# ts7_redraw.net
KiCad netlist of a schematic drawn in EAGLE
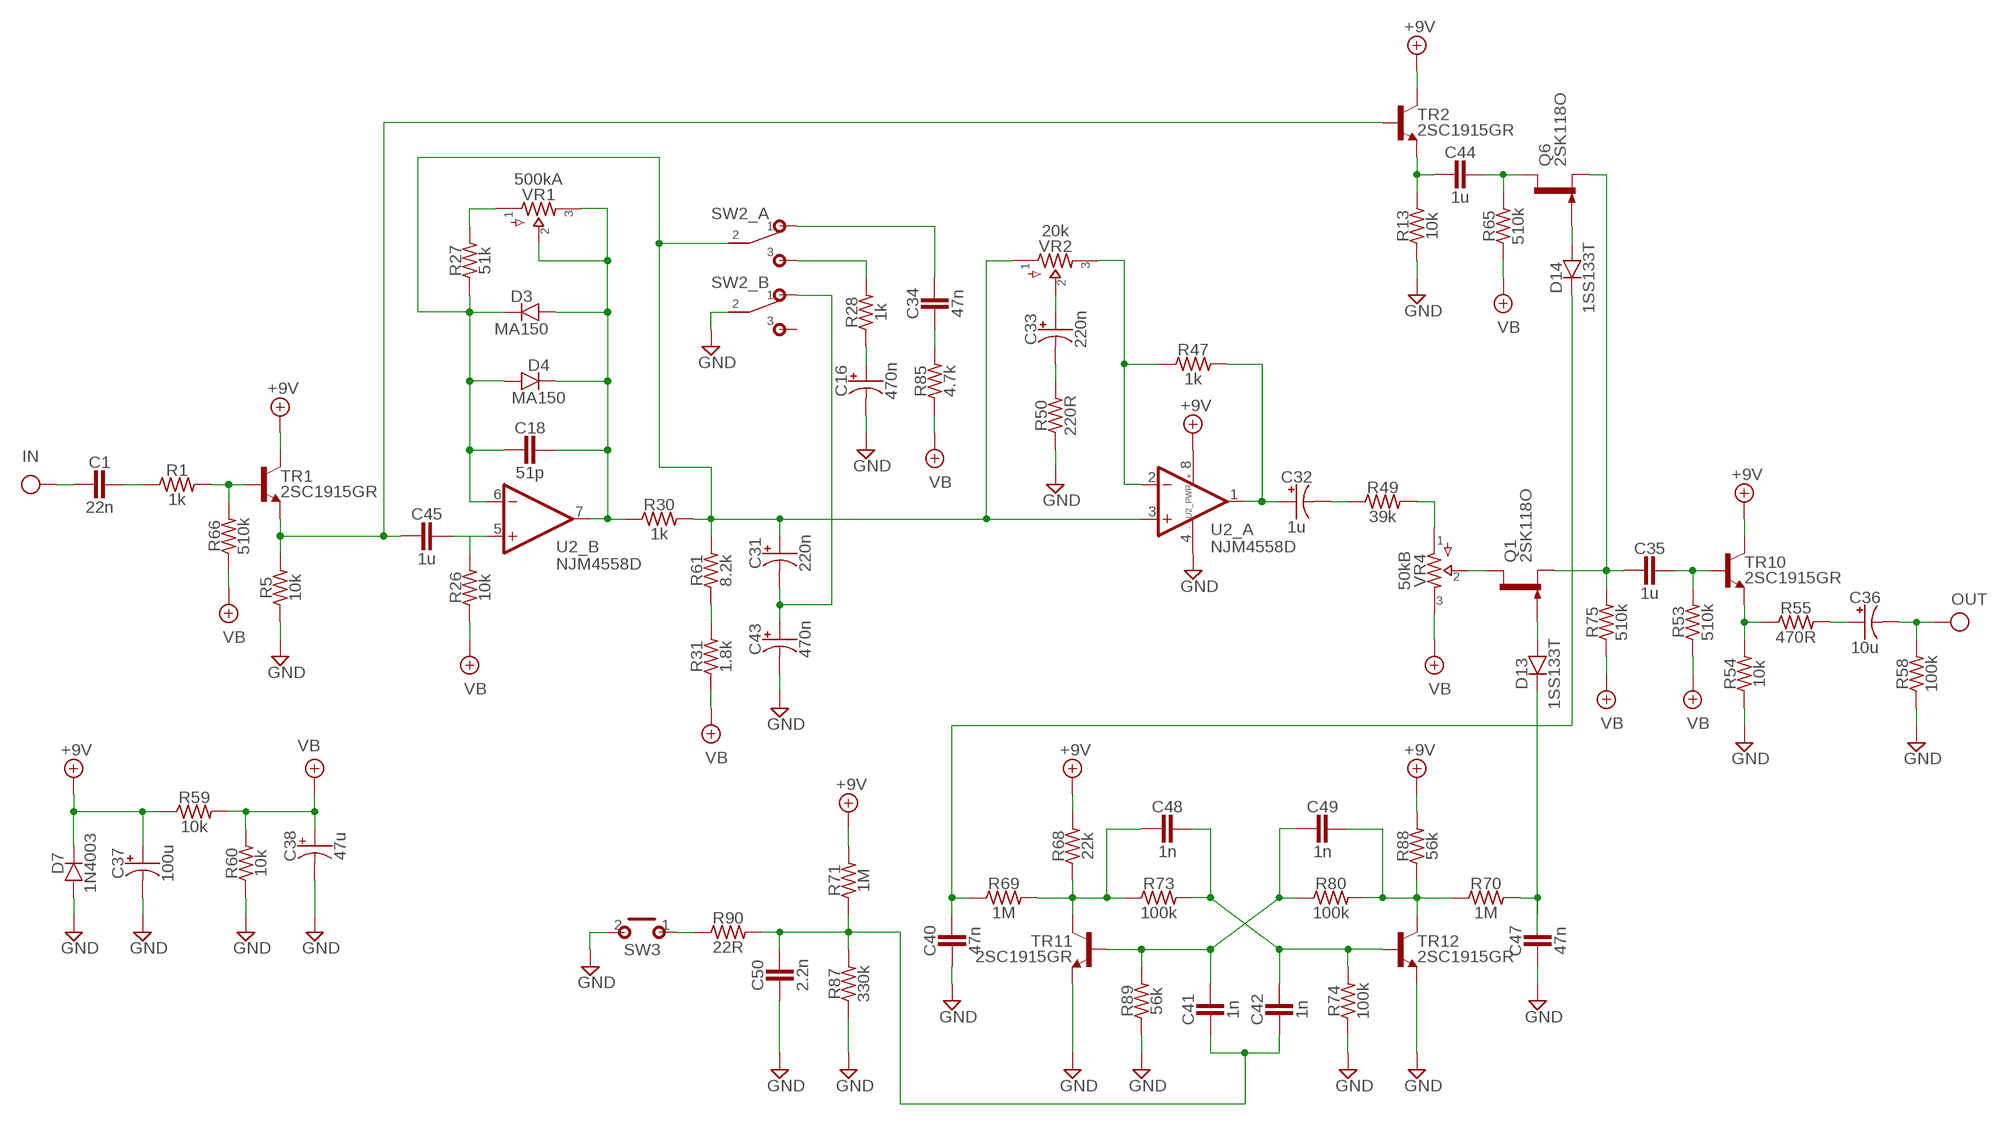
[diagram p0: schematic, sheet 1]

(export (version "E")
  (design (tool "Eeschema 10.0.6"))
  (components
    (comp (ref "C1")
      (value "22n")
      (footprint "eagle-import:BOX_SMALL")
      (libsource (lib "eagle-import") (part "CER/FILMBOX.1"))
    )
    (comp (ref "C16")
      (value "470n")
      (footprint "eagle-import:040_020")
      (libsource (lib "eagle-import") (part "0400"))
    )
    (comp (ref "C18")
      (value "51p")
      (footprint "eagle-import:BOX_SMALL")
      (libsource (lib "eagle-import") (part "CER/FILMBOX.1"))
    )
    (comp (ref "C31")
      (value "220n")
      (footprint "eagle-import:040_020")
      (libsource (lib "eagle-import") (part "0400"))
    )
    (comp (ref "C32")
      (value "1u")
      (footprint "eagle-import:040_020")
      (libsource (lib "eagle-import") (part "0400"))
    )
    (comp (ref "C33")
      (value "220n")
      (footprint "eagle-import:040_020")
      (libsource (lib "eagle-import") (part "0400"))
    )
    (comp (ref "C34")
      (value "47n")
      (footprint "eagle-import:BOX_SMALL")
      (libsource (lib "eagle-import") (part "CER/FILMBOX.1"))
    )
    (comp (ref "C35")
      (value "1u")
      (footprint "eagle-import:BOX_SMALL")
      (libsource (lib "eagle-import") (part "CER/FILMBOX.1"))
    )
    (comp (ref "C36")
      (value "10u")
      (footprint "eagle-import:040_020")
      (libsource (lib "eagle-import") (part "0400"))
    )
    (comp (ref "C37")
      (value "100u")
      (footprint "eagle-import:040_020")
      (libsource (lib "eagle-import") (part "0400"))
    )
    (comp (ref "C38")
      (value "47u")
      (footprint "eagle-import:040_020")
      (libsource (lib "eagle-import") (part "0400"))
    )
    (comp (ref "C40")
      (value "47n")
      (footprint "eagle-import:BOX_SMALL")
      (libsource (lib "eagle-import") (part "CER/FILMBOX.1"))
    )
    (comp (ref "C41")
      (value "1n")
      (footprint "eagle-import:BOX_SMALL")
      (libsource (lib "eagle-import") (part "CER/FILMBOX.1"))
    )
    (comp (ref "C42")
      (value "1n")
      (footprint "eagle-import:BOX_SMALL")
      (libsource (lib "eagle-import") (part "CER/FILMBOX.1"))
    )
    (comp (ref "C43")
      (value "470n")
      (footprint "eagle-import:040_020")
      (libsource (lib "eagle-import") (part "0400"))
    )
    (comp (ref "C44")
      (value "1u")
      (footprint "eagle-import:BOX_SMALL")
      (libsource (lib "eagle-import") (part "CER/FILMBOX.1"))
    )
    (comp (ref "C45")
      (value "1u")
      (footprint "eagle-import:BOX_SMALL")
      (libsource (lib "eagle-import") (part "CER/FILMBOX.1"))
    )
    (comp (ref "C47")
      (value "47n")
      (footprint "eagle-import:BOX_SMALL")
      (libsource (lib "eagle-import") (part "CER/FILMBOX.1"))
    )
    (comp (ref "C48")
      (value "1n")
      (footprint "eagle-import:BOX_SMALL")
      (libsource (lib "eagle-import") (part "CER/FILMBOX.1"))
    )
    (comp (ref "C49")
      (value "1n")
      (footprint "eagle-import:BOX_SMALL")
      (libsource (lib "eagle-import") (part "CER/FILMBOX.1"))
    )
    (comp (ref "C50")
      (value "2.2n")
      (footprint "eagle-import:BOX_SMALL")
      (libsource (lib "eagle-import") (part "CER/FILMBOX.1"))
    )
    (comp (ref "D3")
      (value "MA150")
      (footprint "eagle-import:DO41-2")
      (libsource (lib "eagle-import") (part "DO41.2"))
    )
    (comp (ref "D4")
      (value "MA150")
      (footprint "eagle-import:DO41-2")
      (libsource (lib "eagle-import") (part "DO41.2"))
    )
    (comp (ref "D7")
      (value "1N4003")
      (footprint "eagle-import:DO41-2")
      (libsource (lib "eagle-import") (part "DO41.2"))
    )
    (comp (ref "D13")
      (value "1SS133T")
      (footprint "eagle-import:DO41-2")
      (libsource (lib "eagle-import") (part "DO41.2"))
    )
    (comp (ref "D14")
      (value "1SS133T")
      (footprint "eagle-import:DO41-2")
      (libsource (lib "eagle-import") (part "DO41.2"))
    )
    (comp (ref "Q1")
      (value "2SK118O")
      (footprint "eagle-import:TO92-")
      (libsource (lib "eagle-import") (part "2N5457"))
    )
    (comp (ref "Q6")
      (value "2SK118O")
      (footprint "eagle-import:TO92-")
      (libsource (lib "eagle-import") (part "2N5457"))
    )
    (comp (ref "R1")
      (value "1k")
      (footprint "eagle-import:R0207_3")
      (libsource (lib "eagle-import") (part "R_.3B"))
    )
    (comp (ref "R5")
      (value "10k")
      (footprint "eagle-import:R0207_3")
      (libsource (lib "eagle-import") (part "R_.3B"))
    )
    (comp (ref "R13")
      (value "10k")
      (footprint "eagle-import:R0207_3")
      (libsource (lib "eagle-import") (part "R_.3B"))
    )
    (comp (ref "R26")
      (value "10k")
      (footprint "eagle-import:R0207_3")
      (libsource (lib "eagle-import") (part "R_.3B"))
    )
    (comp (ref "R27")
      (value "51k")
      (footprint "eagle-import:R0207_3")
      (libsource (lib "eagle-import") (part "R_.3B"))
    )
    (comp (ref "R28")
      (value "1k")
      (footprint "eagle-import:R0207_3")
      (libsource (lib "eagle-import") (part "R_.3B"))
    )
    (comp (ref "R30")
      (value "1k")
      (footprint "eagle-import:R0207_3")
      (libsource (lib "eagle-import") (part "R_.3B"))
    )
    (comp (ref "R31")
      (value "1.8k")
      (footprint "eagle-import:R0207_3")
      (libsource (lib "eagle-import") (part "R_.3B"))
    )
    (comp (ref "R47")
      (value "1k")
      (footprint "eagle-import:R0207_3")
      (libsource (lib "eagle-import") (part "R_.3B"))
    )
    (comp (ref "R49")
      (value "39k")
      (footprint "eagle-import:R0207_3")
      (libsource (lib "eagle-import") (part "R_.3B"))
    )
    (comp (ref "R50")
      (value "220R")
      (footprint "eagle-import:R0207_3")
      (libsource (lib "eagle-import") (part "R_.3B"))
    )
    (comp (ref "R53")
      (value "510k")
      (footprint "eagle-import:R0207_3")
      (libsource (lib "eagle-import") (part "R_.3B"))
    )
    (comp (ref "R54")
      (value "10k")
      (footprint "eagle-import:R0207_3")
      (libsource (lib "eagle-import") (part "R_.3B"))
    )
    (comp (ref "R55")
      (value "470R")
      (footprint "eagle-import:R0207_3")
      (libsource (lib "eagle-import") (part "R_.3B"))
    )
    (comp (ref "R58")
      (value "100k")
      (footprint "eagle-import:R0207_3")
      (libsource (lib "eagle-import") (part "R_.3B"))
    )
    (comp (ref "R59")
      (value "10k")
      (footprint "eagle-import:R0207_3")
      (libsource (lib "eagle-import") (part "R_.3B"))
    )
    (comp (ref "R60")
      (value "10k")
      (footprint "eagle-import:R0207_3")
      (libsource (lib "eagle-import") (part "R_.3B"))
    )
    (comp (ref "R61")
      (value "8.2k")
      (footprint "eagle-import:R0207_3")
      (libsource (lib "eagle-import") (part "R_.3B"))
    )
    (comp (ref "R65")
      (value "510k")
      (footprint "eagle-import:R0207_3")
      (libsource (lib "eagle-import") (part "R_.3B"))
    )
    (comp (ref "R66")
      (value "510k")
      (footprint "eagle-import:R0207_3")
      (libsource (lib "eagle-import") (part "R_.3B"))
    )
    (comp (ref "R68")
      (value "22k")
      (footprint "eagle-import:R0207_3")
      (libsource (lib "eagle-import") (part "R_.3B"))
    )
    (comp (ref "R69")
      (value "1M")
      (footprint "eagle-import:R0207_3")
      (libsource (lib "eagle-import") (part "R_.3B"))
    )
    (comp (ref "R70")
      (value "1M")
      (footprint "eagle-import:R0207_3")
      (libsource (lib "eagle-import") (part "R_.3B"))
    )
    (comp (ref "R71")
      (value "1M")
      (footprint "eagle-import:R0207_3")
      (libsource (lib "eagle-import") (part "R_.3B"))
    )
    (comp (ref "R73")
      (value "100k")
      (footprint "eagle-import:R0207_3")
      (libsource (lib "eagle-import") (part "R_.3B"))
    )
    (comp (ref "R74")
      (value "100k")
      (footprint "eagle-import:R0207_3")
      (libsource (lib "eagle-import") (part "R_.3B"))
    )
    (comp (ref "R75")
      (value "510k")
      (footprint "eagle-import:R0207_3")
      (libsource (lib "eagle-import") (part "R_.3B"))
    )
    (comp (ref "R80")
      (value "100k")
      (footprint "eagle-import:R0207_3")
      (libsource (lib "eagle-import") (part "R_.3B"))
    )
    (comp (ref "R85")
      (value "4.7k")
      (footprint "eagle-import:R0207_3")
      (libsource (lib "eagle-import") (part "R_.3B"))
    )
    (comp (ref "R87")
      (value "330k")
      (footprint "eagle-import:R0207_3")
      (libsource (lib "eagle-import") (part "R_.3B"))
    )
    (comp (ref "R88")
      (value "56k")
      (footprint "eagle-import:R0207_3")
      (libsource (lib "eagle-import") (part "R_.3B"))
    )
    (comp (ref "R89")
      (value "56k")
      (footprint "eagle-import:R0207_3")
      (libsource (lib "eagle-import") (part "R_.3B"))
    )
    (comp (ref "R90")
      (value "22R")
      (footprint "eagle-import:R0207_3")
      (libsource (lib "eagle-import") (part "R_.3B"))
    )
    (comp (ref "SW2")
      (value "DPDT")
      (footprint "eagle-import:DPDT")
      (libsource (lib "eagle-import") (part "DPDT"))
    )
    (comp (ref "SW3")
      (value "MOMENTARY")
      (footprint "eagle-import:SPST")
      (libsource (lib "eagle-import") (part "MOMENTARY"))
    )
    (comp (ref "TR1")
      (value "2SC1915GR")
      (footprint "eagle-import:TO92-")
      (libsource (lib "eagle-import") (part "2SC828A"))
    )
    (comp (ref "TR2")
      (value "2SC1915GR")
      (footprint "eagle-import:TO92-")
      (libsource (lib "eagle-import") (part "2SC828A"))
    )
    (comp (ref "TR10")
      (value "2SC1915GR")
      (footprint "eagle-import:TO92-")
      (libsource (lib "eagle-import") (part "2SC828A"))
    )
    (comp (ref "TR11")
      (value "2SC1915GR")
      (footprint "eagle-import:TO92-")
      (libsource (lib "eagle-import") (part "2SC828A"))
    )
    (comp (ref "TR12")
      (value "2SC1915GR")
      (footprint "eagle-import:TO92-")
      (libsource (lib "eagle-import") (part "2SC828A"))
    )
    (comp (ref "U2")
      (value "NJM4558D")
      (footprint "eagle-import:DIL0")
      (libsource (lib "eagle-import") (part "DUALTH"))
    )
    (comp (ref "VR1")
      (value "500kA")
      (footprint "eagle-import:16MM")
      (libsource (lib "eagle-import") (part "POTS16MM"))
    )
    (comp (ref "VR2")
      (value "20k")
      (footprint "eagle-import:16MM")
      (libsource (lib "eagle-import") (part "POTS16MM"))
    )
    (comp (ref "VR4")
      (value "50kB")
      (footprint "eagle-import:16MM")
      (libsource (lib "eagle-import") (part "POTS16MM"))
    )
  )
  (nets
    (net (code "1") (name "+9V") (class "Default")
      (node (ref "C37") (pin "+") (pinfunction "+_+") (pintype "passive"))
      (node (ref "D7") (pin "C") (pinfunction "C_C") (pintype "passive"))
      (node (ref "R59") (pin "1") (pinfunction "1_1") (pintype "passive"))
      (node (ref "R68") (pin "2") (pinfunction "2_2") (pintype "passive"))
      (node (ref "R71") (pin "2") (pinfunction "2_2") (pintype "passive"))
      (node (ref "R88") (pin "2") (pinfunction "2_2") (pintype "passive"))
      (node (ref "TR1") (pin "2") (pinfunction "C_2") (pintype "passive"))
      (node (ref "TR10") (pin "2") (pinfunction "C_2") (pintype "passive"))
      (node (ref "TR2") (pin "2") (pinfunction "C_2") (pintype "passive"))
      (node (ref "U2") (pin "8") (pinfunction "V+_8") (pintype "power_in"))
    )
    (net (code "2") (name "GND") (class "Default")
      (node (ref "C16") (pin "-") (pinfunction "-_-") (pintype "passive"))
      (node (ref "C37") (pin "-") (pinfunction "-_-") (pintype "passive"))
      (node (ref "C38") (pin "-") (pinfunction "-_-") (pintype "passive"))
      (node (ref "C40") (pin "2") (pinfunction "2_2") (pintype "passive"))
      (node (ref "C43") (pin "-") (pinfunction "-_-") (pintype "passive"))
      (node (ref "C47") (pin "2") (pinfunction "2_2") (pintype "passive"))
      (node (ref "C50") (pin "2") (pinfunction "2_2") (pintype "passive"))
      (node (ref "D7") (pin "A") (pinfunction "A_A") (pintype "passive"))
      (node (ref "R13") (pin "1") (pinfunction "1_1") (pintype "passive"))
      (node (ref "R5") (pin "1") (pinfunction "1_1") (pintype "passive"))
      (node (ref "R50") (pin "1") (pinfunction "1_1") (pintype "passive"))
      (node (ref "R54") (pin "1") (pinfunction "1_1") (pintype "passive"))
      (node (ref "R58") (pin "1") (pinfunction "1_1") (pintype "passive"))
      (node (ref "R60") (pin "1") (pinfunction "1_1") (pintype "passive"))
      (node (ref "R74") (pin "1") (pinfunction "1_1") (pintype "passive"))
      (node (ref "R87") (pin "1") (pinfunction "1_1") (pintype "passive"))
      (node (ref "R89") (pin "1") (pinfunction "1_1") (pintype "passive"))
      (node (ref "SW2") (pin "B2") (pinfunction "2_B2") (pintype "passive"))
      (node (ref "SW3") (pin "2") (pinfunction "S_2") (pintype "passive"))
      (node (ref "TR11") (pin "3") (pinfunction "E_3") (pintype "passive"))
      (node (ref "TR12") (pin "3") (pinfunction "E_3") (pintype "passive"))
      (node (ref "U2") (pin "4") (pinfunction "V-_4") (pintype "power_in"))
    )
    (net (code "3") (name "IN") (class "Default")
      (node (ref "C1") (pin "2") (pinfunction "2_2") (pintype "passive"))
    )
    (net (code "4") (name "Net-(C1-Pad1)") (class "Default")
      (node (ref "C1") (pin "1") (pinfunction "1_1") (pintype "passive"))
      (node (ref "R1") (pin "1") (pinfunction "1_1") (pintype "passive"))
    )
    (net (code "5") (name "Net-(C16-Pad+)") (class "Default")
      (node (ref "C16") (pin "+") (pinfunction "+_+") (pintype "passive"))
      (node (ref "R28") (pin "1") (pinfunction "1_1") (pintype "passive"))
    )
    (net (code "6") (name "Net-(C32-Pad-)") (class "Default")
      (node (ref "C32") (pin "-") (pinfunction "-_-") (pintype "passive"))
      (node (ref "R49") (pin "1") (pinfunction "1_1") (pintype "passive"))
    )
    (net (code "7") (name "Net-(C33-Pad+)") (class "Default")
      (node (ref "C33") (pin "+") (pinfunction "+_+") (pintype "passive"))
      (node (ref "VR2") (pin "2") (pinfunction "2_2") (pintype "passive"))
    )
    (net (code "8") (name "Net-(C33-Pad-)") (class "Default")
      (node (ref "C33") (pin "-") (pinfunction "-_-") (pintype "passive"))
      (node (ref "R50") (pin "2") (pinfunction "2_2") (pintype "passive"))
    )
    (net (code "9") (name "Net-(C34-Pad2)") (class "Default")
      (node (ref "C34") (pin "2") (pinfunction "2_2") (pintype "passive"))
      (node (ref "R85") (pin "2") (pinfunction "2_2") (pintype "passive"))
    )
    (net (code "10") (name "Net-(C36-Pad+)") (class "Default")
      (node (ref "C36") (pin "+") (pinfunction "+_+") (pintype "passive"))
      (node (ref "R55") (pin "2") (pinfunction "2_2") (pintype "passive"))
    )
    (net (code "11") (name "Net-(C40-Pad1)") (class "Default")
      (node (ref "C40") (pin "1") (pinfunction "1_1") (pintype "passive"))
      (node (ref "D14") (pin "C") (pinfunction "C_C") (pintype "passive"))
      (node (ref "R69") (pin "1") (pinfunction "1_1") (pintype "passive"))
    )
    (net (code "12") (name "Net-(C41-Pad2)") (class "Default")
      (node (ref "C41") (pin "2") (pinfunction "2_2") (pintype "passive"))
      (node (ref "C42") (pin "2") (pinfunction "2_2") (pintype "passive"))
      (node (ref "C50") (pin "1") (pinfunction "1_1") (pintype "passive"))
      (node (ref "R71") (pin "1") (pinfunction "1_1") (pintype "passive"))
      (node (ref "R87") (pin "2") (pinfunction "2_2") (pintype "passive"))
      (node (ref "R90") (pin "2") (pinfunction "2_2") (pintype "passive"))
    )
    (net (code "13") (name "Net-(C47-Pad1)") (class "Default")
      (node (ref "C47") (pin "1") (pinfunction "1_1") (pintype "passive"))
      (node (ref "D13") (pin "C") (pinfunction "C_C") (pintype "passive"))
      (node (ref "R70") (pin "2") (pinfunction "2_2") (pintype "passive"))
    )
    (net (code "14") (name "Net-(Q1-D)") (class "Default")
      (node (ref "Q1") (pin "3") (pinfunction "D_3") (pintype "passive"))
      (node (ref "VR4") (pin "2") (pinfunction "2_2") (pintype "passive"))
    )
    (net (code "15") (name "Net-(Q1-G)") (class "Default")
      (node (ref "D13") (pin "A") (pinfunction "A_A") (pintype "passive"))
      (node (ref "Q1") (pin "1") (pinfunction "G_1") (pintype "passive"))
    )
    (net (code "16") (name "Net-(Q1-S)") (class "Default")
      (node (ref "C35") (pin "2") (pinfunction "2_2") (pintype "passive"))
      (node (ref "Q1") (pin "2") (pinfunction "S_2") (pintype "passive"))
      (node (ref "Q6") (pin "2") (pinfunction "S_2") (pintype "passive"))
      (node (ref "R75") (pin "2") (pinfunction "2_2") (pintype "passive"))
    )
    (net (code "17") (name "Net-(Q6-D)") (class "Default")
      (node (ref "C44") (pin "1") (pinfunction "1_1") (pintype "passive"))
      (node (ref "Q6") (pin "3") (pinfunction "D_3") (pintype "passive"))
      (node (ref "R65") (pin "2") (pinfunction "2_2") (pintype "passive"))
    )
    (net (code "18") (name "Net-(Q6-G)") (class "Default")
      (node (ref "D14") (pin "A") (pinfunction "A_A") (pintype "passive"))
      (node (ref "Q6") (pin "1") (pinfunction "G_1") (pintype "passive"))
    )
    (net (code "19") (name "Net-(R27-Pad2)") (class "Default")
      (node (ref "R27") (pin "2") (pinfunction "2_2") (pintype "passive"))
      (node (ref "VR1") (pin "1") (pinfunction "1_1") (pintype "passive"))
    )
    (net (code "20") (name "Net-(R31-Pad2)") (class "Default")
      (node (ref "R31") (pin "2") (pinfunction "2_2") (pintype "passive"))
      (node (ref "R61") (pin "1") (pinfunction "1_1") (pintype "passive"))
    )
    (net (code "21") (name "Net-(R49-Pad2)") (class "Default")
      (node (ref "R49") (pin "2") (pinfunction "2_2") (pintype "passive"))
      (node (ref "VR4") (pin "1") (pinfunction "1_1") (pintype "passive"))
    )
    (net (code "22") (name "Net-(SW2A-1)") (class "Default")
      (node (ref "C34") (pin "1") (pinfunction "1_1") (pintype "passive"))
      (node (ref "SW2") (pin "A1") (pinfunction "1_A1") (pintype "passive"))
    )
    (net (code "23") (name "Net-(SW2A-2)") (class "Default")
      (node (ref "C18") (pin "2") (pinfunction "2_2") (pintype "passive"))
      (node (ref "C31") (pin "+") (pinfunction "+_+") (pintype "passive"))
      (node (ref "D3") (pin "C") (pinfunction "C_C") (pintype "passive"))
      (node (ref "D4") (pin "A") (pinfunction "A_A") (pintype "passive"))
      (node (ref "R27") (pin "1") (pinfunction "1_1") (pintype "passive"))
      (node (ref "R30") (pin "2") (pinfunction "2_2") (pintype "passive"))
      (node (ref "R61") (pin "2") (pinfunction "2_2") (pintype "passive"))
      (node (ref "SW2") (pin "A2") (pinfunction "2_A2") (pintype "passive"))
      (node (ref "U2") (pin "3") (pinfunction "+IN_3") (pintype "input"))
      (node (ref "U2") (pin "6") (pinfunction "-IN_6") (pintype "input"))
      (node (ref "VR2") (pin "1") (pinfunction "1_1") (pintype "passive"))
    )
    (net (code "24") (name "Net-(SW2A-3)") (class "Default")
      (node (ref "R28") (pin "2") (pinfunction "2_2") (pintype "passive"))
      (node (ref "SW2") (pin "A3") (pinfunction "3_A3") (pintype "passive"))
    )
    (net (code "25") (name "Net-(SW2B-1)") (class "Default")
      (node (ref "C31") (pin "-") (pinfunction "-_-") (pintype "passive"))
      (node (ref "C43") (pin "+") (pinfunction "+_+") (pintype "passive"))
      (node (ref "SW2") (pin "B1") (pinfunction "1_B1") (pintype "passive"))
    )
    (net (code "26") (name "Net-(SW3-P)") (class "Default")
      (node (ref "R90") (pin "1") (pinfunction "1_1") (pintype "passive"))
      (node (ref "SW3") (pin "1") (pinfunction "P_1") (pintype "passive"))
    )
    (net (code "27") (name "Net-(TR1-B)") (class "Default")
      (node (ref "R1") (pin "2") (pinfunction "2_2") (pintype "passive"))
      (node (ref "R66") (pin "2") (pinfunction "2_2") (pintype "passive"))
      (node (ref "TR1") (pin "1") (pinfunction "B_1") (pintype "passive"))
    )
    (net (code "28") (name "Net-(TR1-E)") (class "Default")
      (node (ref "C45") (pin "2") (pinfunction "2_2") (pintype "passive"))
      (node (ref "R5") (pin "2") (pinfunction "2_2") (pintype "passive"))
      (node (ref "TR1") (pin "3") (pinfunction "E_3") (pintype "passive"))
      (node (ref "TR2") (pin "1") (pinfunction "B_1") (pintype "passive"))
    )
    (net (code "29") (name "Net-(TR2-E)") (class "Default")
      (node (ref "C44") (pin "2") (pinfunction "2_2") (pintype "passive"))
      (node (ref "R13") (pin "2") (pinfunction "2_2") (pintype "passive"))
      (node (ref "TR2") (pin "3") (pinfunction "E_3") (pintype "passive"))
    )
    (net (code "30") (name "Net-(TR10-B)") (class "Default")
      (node (ref "C35") (pin "1") (pinfunction "1_1") (pintype "passive"))
      (node (ref "R53") (pin "2") (pinfunction "2_2") (pintype "passive"))
      (node (ref "TR10") (pin "1") (pinfunction "B_1") (pintype "passive"))
    )
    (net (code "31") (name "Net-(TR10-E)") (class "Default")
      (node (ref "R54") (pin "2") (pinfunction "2_2") (pintype "passive"))
      (node (ref "R55") (pin "1") (pinfunction "1_1") (pintype "passive"))
      (node (ref "TR10") (pin "3") (pinfunction "E_3") (pintype "passive"))
    )
    (net (code "32") (name "Net-(TR11-B)") (class "Default")
      (node (ref "C41") (pin "1") (pinfunction "1_1") (pintype "passive"))
      (node (ref "C49") (pin "2") (pinfunction "2_2") (pintype "passive"))
      (node (ref "R80") (pin "1") (pinfunction "1_1") (pintype "passive"))
      (node (ref "R89") (pin "2") (pinfunction "2_2") (pintype "passive"))
      (node (ref "TR11") (pin "1") (pinfunction "B_1") (pintype "passive"))
    )
    (net (code "33") (name "Net-(TR11-C)") (class "Default")
      (node (ref "C48") (pin "2") (pinfunction "2_2") (pintype "passive"))
      (node (ref "R68") (pin "1") (pinfunction "1_1") (pintype "passive"))
      (node (ref "R69") (pin "2") (pinfunction "2_2") (pintype "passive"))
      (node (ref "R73") (pin "1") (pinfunction "1_1") (pintype "passive"))
      (node (ref "TR11") (pin "2") (pinfunction "C_2") (pintype "passive"))
    )
    (net (code "34") (name "Net-(TR12-B)") (class "Default")
      (node (ref "C42") (pin "1") (pinfunction "1_1") (pintype "passive"))
      (node (ref "C48") (pin "1") (pinfunction "1_1") (pintype "passive"))
      (node (ref "R73") (pin "2") (pinfunction "2_2") (pintype "passive"))
      (node (ref "R74") (pin "2") (pinfunction "2_2") (pintype "passive"))
      (node (ref "TR12") (pin "1") (pinfunction "B_1") (pintype "passive"))
    )
    (net (code "35") (name "Net-(TR12-C)") (class "Default")
      (node (ref "C49") (pin "1") (pinfunction "1_1") (pintype "passive"))
      (node (ref "R70") (pin "1") (pinfunction "1_1") (pintype "passive"))
      (node (ref "R80") (pin "2") (pinfunction "2_2") (pintype "passive"))
      (node (ref "R88") (pin "1") (pinfunction "1_1") (pintype "passive"))
      (node (ref "TR12") (pin "2") (pinfunction "C_2") (pintype "passive"))
    )
    (net (code "36") (name "Net-(U2A--IN)") (class "Default")
      (node (ref "R47") (pin "1") (pinfunction "1_1") (pintype "passive"))
      (node (ref "U2") (pin "2") (pinfunction "-IN_2") (pintype "input"))
      (node (ref "VR2") (pin "3") (pinfunction "3_3") (pintype "passive"))
    )
    (net (code "37") (name "Net-(U2A-OUT)") (class "Default")
      (node (ref "C32") (pin "+") (pinfunction "+_+") (pintype "passive"))
      (node (ref "R47") (pin "2") (pinfunction "2_2") (pintype "passive"))
      (node (ref "U2") (pin "1") (pinfunction "OUT_1") (pintype "output"))
    )
    (net (code "38") (name "Net-(U2B-+IN)") (class "Default")
      (node (ref "C45") (pin "1") (pinfunction "1_1") (pintype "passive"))
      (node (ref "R26") (pin "2") (pinfunction "2_2") (pintype "passive"))
      (node (ref "U2") (pin "5") (pinfunction "+IN_5") (pintype "input"))
    )
    (net (code "39") (name "Net-(U2B-OUT)") (class "Default")
      (node (ref "C18") (pin "1") (pinfunction "1_1") (pintype "passive"))
      (node (ref "D3") (pin "A") (pinfunction "A_A") (pintype "passive"))
      (node (ref "D4") (pin "C") (pinfunction "C_C") (pintype "passive"))
      (node (ref "R30") (pin "1") (pinfunction "1_1") (pintype "passive"))
      (node (ref "U2") (pin "7") (pinfunction "OUT_7") (pintype "output"))
      (node (ref "VR1") (pin "2") (pinfunction "2_2") (pintype "passive"))
      (node (ref "VR1") (pin "3") (pinfunction "3_3") (pintype "passive"))
    )
    (net (code "40") (name "OUT") (class "Default")
      (node (ref "C36") (pin "-") (pinfunction "-_-") (pintype "passive"))
      (node (ref "R58") (pin "2") (pinfunction "2_2") (pintype "passive"))
    )
    (net (code "41") (name "VB") (class "Default")
      (node (ref "C38") (pin "+") (pinfunction "+_+") (pintype "passive"))
      (node (ref "R26") (pin "1") (pinfunction "1_1") (pintype "passive"))
      (node (ref "R31") (pin "1") (pinfunction "1_1") (pintype "passive"))
      (node (ref "R53") (pin "1") (pinfunction "1_1") (pintype "passive"))
      (node (ref "R59") (pin "2") (pinfunction "2_2") (pintype "passive"))
      (node (ref "R60") (pin "2") (pinfunction "2_2") (pintype "passive"))
      (node (ref "R65") (pin "1") (pinfunction "1_1") (pintype "passive"))
      (node (ref "R66") (pin "1") (pinfunction "1_1") (pintype "passive"))
      (node (ref "R75") (pin "1") (pinfunction "1_1") (pintype "passive"))
      (node (ref "R85") (pin "1") (pinfunction "1_1") (pintype "passive"))
      (node (ref "VR4") (pin "3") (pinfunction "3_3") (pintype "passive"))
    )
    (net (code "42") (name "unconnected-(SW2B-3-PadB3)") (class "Default")
      (node (ref "SW2") (pin "B3") (pinfunction "3_B3") (pintype "passive"))
    )
  )
)
